# Power_Connections.net
KiCad netlist of a schematic drawn in Altium Designer
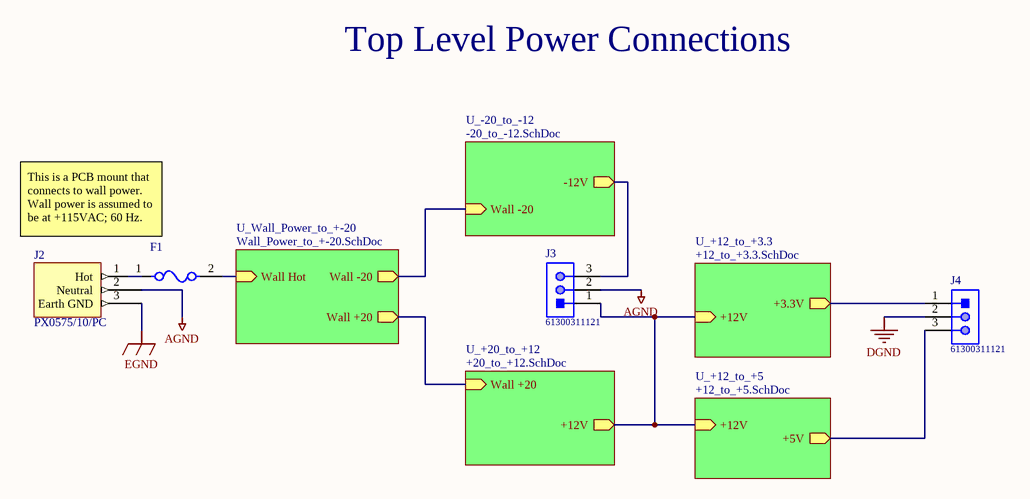
[diagram p0: Power_Connections.SchDoc]

(export (version "E")
  (design (tool "Eeschema 10.0.6"))
  (components
    (comp (ref "F1")
      (value "C1F 3")
      (footprint "FP-0466-MFG")
      (description "FUSE BOARD MNT 200MA 125VAC/VDC")
      (libsource (lib "Altium Content Vault") (part "5bcf9b9f640e542cf0359d10258e979"))
    )
    (comp (ref "J2")
      (value "PX0575/10/PC")
      (footprint "PCBComponent_1")
      (description "Conn Inlet M 3 POS 9.17mm Solder RA Thru-Hole 3 Terminal 1 Port Bulk")
      (libsource (lib "California Institute of Technology") (part "New symbol 1"))
    )
    (comp (ref "J3")
      (value "61300311121")
      (footprint "61300311121")
      (description "THT Vertical Pin Header WR-PHD, Pitch 2.54 mm, Single Row, 3 pins")
      (fields (field (name "MANUFACTURER") "Wurth Elektronik") (field (name "PUBLISHER") "WurthElektronik"))
      (libsource (lib "") (part "WE-CN-1P-M-R3_1"))
    )
    (comp (ref "J4")
      (value "61300311121")
      (footprint "61300311121")
      (description "THT Vertical Pin Header WR-PHD, Pitch 2.54 mm, Single Row, 3 pins")
      (fields (field (name "MANUFACTURER") "Wurth Elektronik") (field (name "PUBLISHER") "WurthElektronik"))
      (libsource (lib "Altium Content Vault") (part "WE-CN-1P-M-R3"))
    )
  )
  (nets
    (net (code "1") (name "/+3.3V") (class "Default")
      (node (ref "J4") (pin "1") (pinfunction "1_1") (pintype "passive"))
    )
    (net (code "2") (name "/+5V") (class "Default")
      (node (ref "J4") (pin "3") (pinfunction "3_3") (pintype "passive"))
    )
    (net (code "3") (name "/+12V") (class "Default")
      (node (ref "J3") (pin "1") (pinfunction "1_1") (pintype "passive"))
    )
    (net (code "4") (name "/-12V") (class "Default")
      (node (ref "J3") (pin "3") (pinfunction "3_3") (pintype "passive"))
    )
    (net (code "7") (name "/Wall Hot") (class "Default")
      (node (ref "F1") (pin "2") (pinfunction "2_2") (pintype "passive"))
    )
    (net (code "8") (name "AGND") (class "Default")
      (node (ref "J2") (pin "2") (pinfunction "Neutral_2") (pintype "output"))
      (node (ref "J3") (pin "2") (pinfunction "2_2") (pintype "passive"))
    )
    (net (code "9") (name "DGND") (class "Default")
      (node (ref "J4") (pin "2") (pinfunction "2_2") (pintype "passive"))
    )
    (net (code "10") (name "EGND") (class "Default")
      (node (ref "J2") (pin "3") (pinfunction "Earth_GND_3") (pintype "output"))
    )
    (net (code "11") (name "Net-(J2-Hot)") (class "Default")
      (node (ref "F1") (pin "1") (pinfunction "1_1") (pintype "passive"))
      (node (ref "J2") (pin "1") (pinfunction "Hot_1") (pintype "output"))
    )
  )
)
